# BAI4.net
KiCad netlist of a schematic drawn in Altium Designer
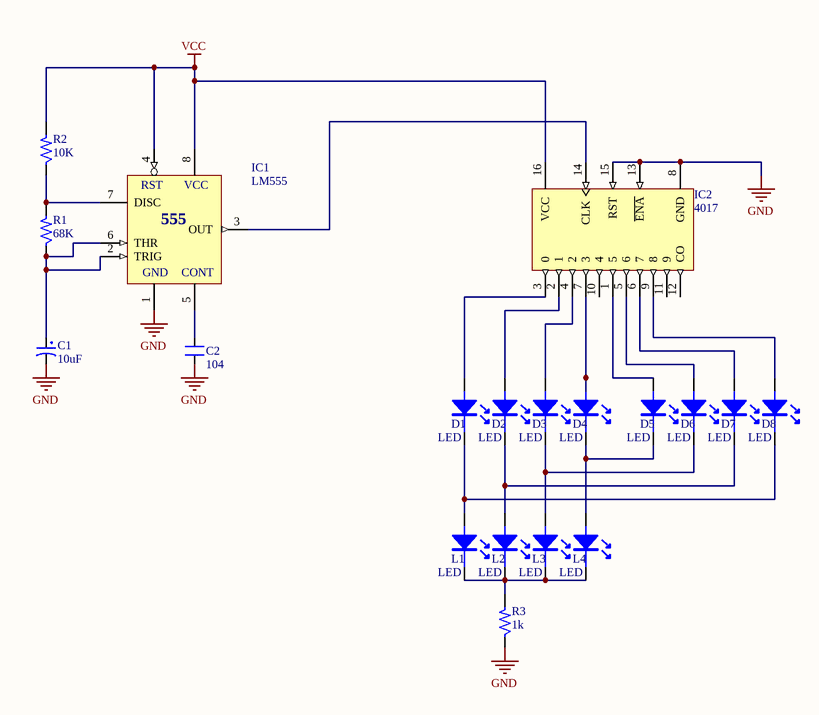
[diagram p0: BAI4.SchDoc]

(export (version "E")
  (design (tool "Eeschema 10.0.6"))
  (components
    (comp (ref "C1")
      (value "10uF")
      (footprint "CP1/2")
      (description "Cap P  0,1uF < 22uF , 16 - 50V")
      (libsource (lib "Cty1") (part "CP1"))
    )
    (comp (ref "C2")
      (value "104")
      (footprint "SM-0805")
      (description "Cap SMD")
      (libsource (lib "Cty1") (part "CM"))
    )
    (comp (ref "D1") (value "LED") (footprint "CAP10UF") (libsource (lib "Cty1") (part "LED")))
    (comp (ref "D2") (value "LED") (footprint "CAP10UF") (libsource (lib "Cty1") (part "LED")))
    (comp (ref "D3") (value "LED") (footprint "CAP10UF") (libsource (lib "Cty1") (part "LED")))
    (comp (ref "D4") (value "LED") (footprint "CAP10UF") (libsource (lib "Cty1") (part "LED")))
    (comp (ref "D5") (value "LED") (footprint "CAP10UF") (libsource (lib "Cty1") (part "LED")))
    (comp (ref "D6") (value "LED") (footprint "CAP10UF") (libsource (lib "Cty1") (part "LED")))
    (comp (ref "D7") (value "LED") (footprint "CAP10UF") (libsource (lib "Cty1") (part "LED")))
    (comp (ref "D8") (value "LED") (footprint "CAP10UF") (libsource (lib "Cty1") (part "LED")))
    (comp (ref "IC1")
      (value "LM555")
      (footprint "DIP8")
      (description "Timer Circuits")
      (libsource (lib "Cty1") (part "LM555"))
    )
    (comp (ref "IC2")
      (value "4017")
      (footprint "DIP16")
      (description "Decade Counter/Divider with 10 Decoded Outputs")
      (fields (field (name "DESIGNED BY") "VanDungEvn"))
      (libsource (lib "Cty1") (part "4017"))
    )
    (comp (ref "L1") (value "LED") (footprint "CAP10UF") (libsource (lib "Cty1") (part "LED")))
    (comp (ref "L2") (value "LED") (footprint "CAP10UF") (libsource (lib "Cty1") (part "LED")))
    (comp (ref "L3") (value "LED") (footprint "CAP10UF") (libsource (lib "Cty1") (part "LED")))
    (comp (ref "L4") (value "LED") (footprint "CAP10UF") (libsource (lib "Cty1") (part "LED")))
    (comp (ref "R1")
      (value "68K")
      (footprint "R1/6W")
      (description "Resistor 1/4W")
      (libsource (lib "Cty1") (part "Res"))
    )
    (comp (ref "R2")
      (value "10K")
      (footprint "R1/6W")
      (description "Resistor 1/4W")
      (libsource (lib "Cty1") (part "Res"))
    )
    (comp (ref "R3")
      (value "1k")
      (footprint "R1/6W")
      (description "Resistor 1/4W")
      (libsource (lib "Cty1") (part "Res"))
    )
  )
  (nets
    (net (code "1") (name "GND") (class "Default")
      (node (ref "C1") (pin "2") (pinfunction "2_2") (pintype "passive"))
      (node (ref "C2") (pin "1") (pinfunction "1_1") (pintype "passive"))
      (node (ref "IC1") (pin "1") (pinfunction "GND_1") (pintype "power_in"))
      (node (ref "IC2") (pin "13") (pinfunction "~{ENA}_13") (pintype "input"))
      (node (ref "IC2") (pin "15") (pinfunction "RST_15") (pintype "input"))
      (node (ref "IC2") (pin "8") (pinfunction "GND_8") (pintype "power_in"))
      (node (ref "R3") (pin "1") (pinfunction "1_1") (pintype "passive"))
    )
    (net (code "2") (name "Net-(D1-Pad2)") (class "Default")
      (node (ref "D1") (pin "2") (pinfunction "2_2") (pintype "passive"))
      (node (ref "D8") (pin "2") (pinfunction "2_2") (pintype "passive"))
      (node (ref "L1") (pin "1") (pinfunction "1_1") (pintype "passive"))
    )
    (net (code "3") (name "Net-(D2-Pad2)") (class "Default")
      (node (ref "D2") (pin "2") (pinfunction "2_2") (pintype "passive"))
      (node (ref "D7") (pin "2") (pinfunction "2_2") (pintype "passive"))
      (node (ref "L2") (pin "1") (pinfunction "1_1") (pintype "passive"))
    )
    (net (code "4") (name "Net-(D3-Pad2)") (class "Default")
      (node (ref "D3") (pin "2") (pinfunction "2_2") (pintype "passive"))
      (node (ref "D6") (pin "2") (pinfunction "2_2") (pintype "passive"))
      (node (ref "L3") (pin "1") (pinfunction "1_1") (pintype "passive"))
    )
    (net (code "5") (name "Net-(D4-Pad2)") (class "Default")
      (node (ref "D4") (pin "2") (pinfunction "2_2") (pintype "passive"))
      (node (ref "D5") (pin "2") (pinfunction "2_2") (pintype "passive"))
      (node (ref "L4") (pin "1") (pinfunction "1_1") (pintype "passive"))
    )
    (net (code "6") (name "Net-(IC1-CONT)") (class "Default")
      (node (ref "C2") (pin "2") (pinfunction "2_2") (pintype "passive"))
      (node (ref "IC1") (pin "5") (pinfunction "CONT_5") (pintype "passive"))
    )
    (net (code "7") (name "Net-(IC1-DISC)") (class "Default")
      (node (ref "IC1") (pin "7") (pinfunction "DISC_7") (pintype "open_collector"))
      (node (ref "R1") (pin "2") (pinfunction "2_2") (pintype "passive"))
      (node (ref "R2") (pin "1") (pinfunction "1_1") (pintype "passive"))
    )
    (net (code "8") (name "Net-(IC1-OUT)") (class "Default")
      (node (ref "IC1") (pin "3") (pinfunction "OUT_3") (pintype "output"))
      (node (ref "IC2") (pin "14") (pinfunction "CLK_14") (pintype "input"))
    )
    (net (code "9") (name "Net-(IC1-THR)") (class "Default")
      (node (ref "C1") (pin "1") (pinfunction "1_1") (pintype "passive"))
      (node (ref "IC1") (pin "2") (pinfunction "TRIG_2") (pintype "input"))
      (node (ref "IC1") (pin "6") (pinfunction "THR_6") (pintype "input"))
      (node (ref "R1") (pin "1") (pinfunction "1_1") (pintype "passive"))
    )
    (net (code "10") (name "Net-(IC2-0)") (class "Default")
      (node (ref "D1") (pin "1") (pinfunction "1_1") (pintype "passive"))
      (node (ref "IC2") (pin "3") (pinfunction "0_3") (pintype "output"))
    )
    (net (code "11") (name "Net-(IC2-1)") (class "Default")
      (node (ref "D2") (pin "1") (pinfunction "1_1") (pintype "passive"))
      (node (ref "IC2") (pin "2") (pinfunction "1_2") (pintype "output"))
    )
    (net (code "12") (name "Net-(IC2-2)") (class "Default")
      (node (ref "D3") (pin "1") (pinfunction "1_1") (pintype "passive"))
      (node (ref "IC2") (pin "4") (pinfunction "2_4") (pintype "output"))
    )
    (net (code "13") (name "Net-(IC2-3)") (class "Default")
      (node (ref "D4") (pin "1") (pinfunction "1_1") (pintype "passive"))
      (node (ref "IC2") (pin "7") (pinfunction "3_7") (pintype "output"))
    )
    (net (code "14") (name "Net-(IC2-5)") (class "Default")
      (node (ref "D5") (pin "1") (pinfunction "1_1") (pintype "passive"))
      (node (ref "IC2") (pin "1") (pinfunction "5_1") (pintype "output"))
    )
    (net (code "15") (name "Net-(IC2-6)") (class "Default")
      (node (ref "D6") (pin "1") (pinfunction "1_1") (pintype "passive"))
      (node (ref "IC2") (pin "5") (pinfunction "6_5") (pintype "output"))
    )
    (net (code "16") (name "Net-(IC2-7)") (class "Default")
      (node (ref "D7") (pin "1") (pinfunction "1_1") (pintype "passive"))
      (node (ref "IC2") (pin "6") (pinfunction "7_6") (pintype "output"))
    )
    (net (code "17") (name "Net-(IC2-8)") (class "Default")
      (node (ref "D8") (pin "1") (pinfunction "1_1") (pintype "passive"))
      (node (ref "IC2") (pin "9") (pinfunction "8_9") (pintype "output"))
    )
    (net (code "18") (name "Net-(L1-Pad2)") (class "Default")
      (node (ref "L1") (pin "2") (pinfunction "2_2") (pintype "passive"))
      (node (ref "L2") (pin "2") (pinfunction "2_2") (pintype "passive"))
      (node (ref "L3") (pin "2") (pinfunction "2_2") (pintype "passive"))
      (node (ref "L4") (pin "2") (pinfunction "2_2") (pintype "passive"))
      (node (ref "R3") (pin "2") (pinfunction "2_2") (pintype "passive"))
    )
    (net (code "19") (name "VCC") (class "Default")
      (node (ref "IC1") (pin "4") (pinfunction "RST_4") (pintype "input"))
      (node (ref "IC1") (pin "8") (pinfunction "VCC_8") (pintype "power_in"))
      (node (ref "IC2") (pin "16") (pinfunction "VCC_16") (pintype "power_in"))
      (node (ref "R2") (pin "2") (pinfunction "2_2") (pintype "passive"))
    )
    (net (code "20") (name "unconnected-(IC2-4-Pad10)") (class "Default")
      (node (ref "IC2") (pin "10") (pinfunction "4_10") (pintype "output"))
    )
    (net (code "21") (name "unconnected-(IC2-9-Pad11)") (class "Default")
      (node (ref "IC2") (pin "11") (pinfunction "9_11") (pintype "output"))
    )
    (net (code "22") (name "unconnected-(IC2-CO-Pad12)") (class "Default")
      (node (ref "IC2") (pin "12") (pinfunction "CO_12") (pintype "output"))
    )
  )
)
